# Front_End.net
KiCad netlist of a schematic drawn in Altium Designer
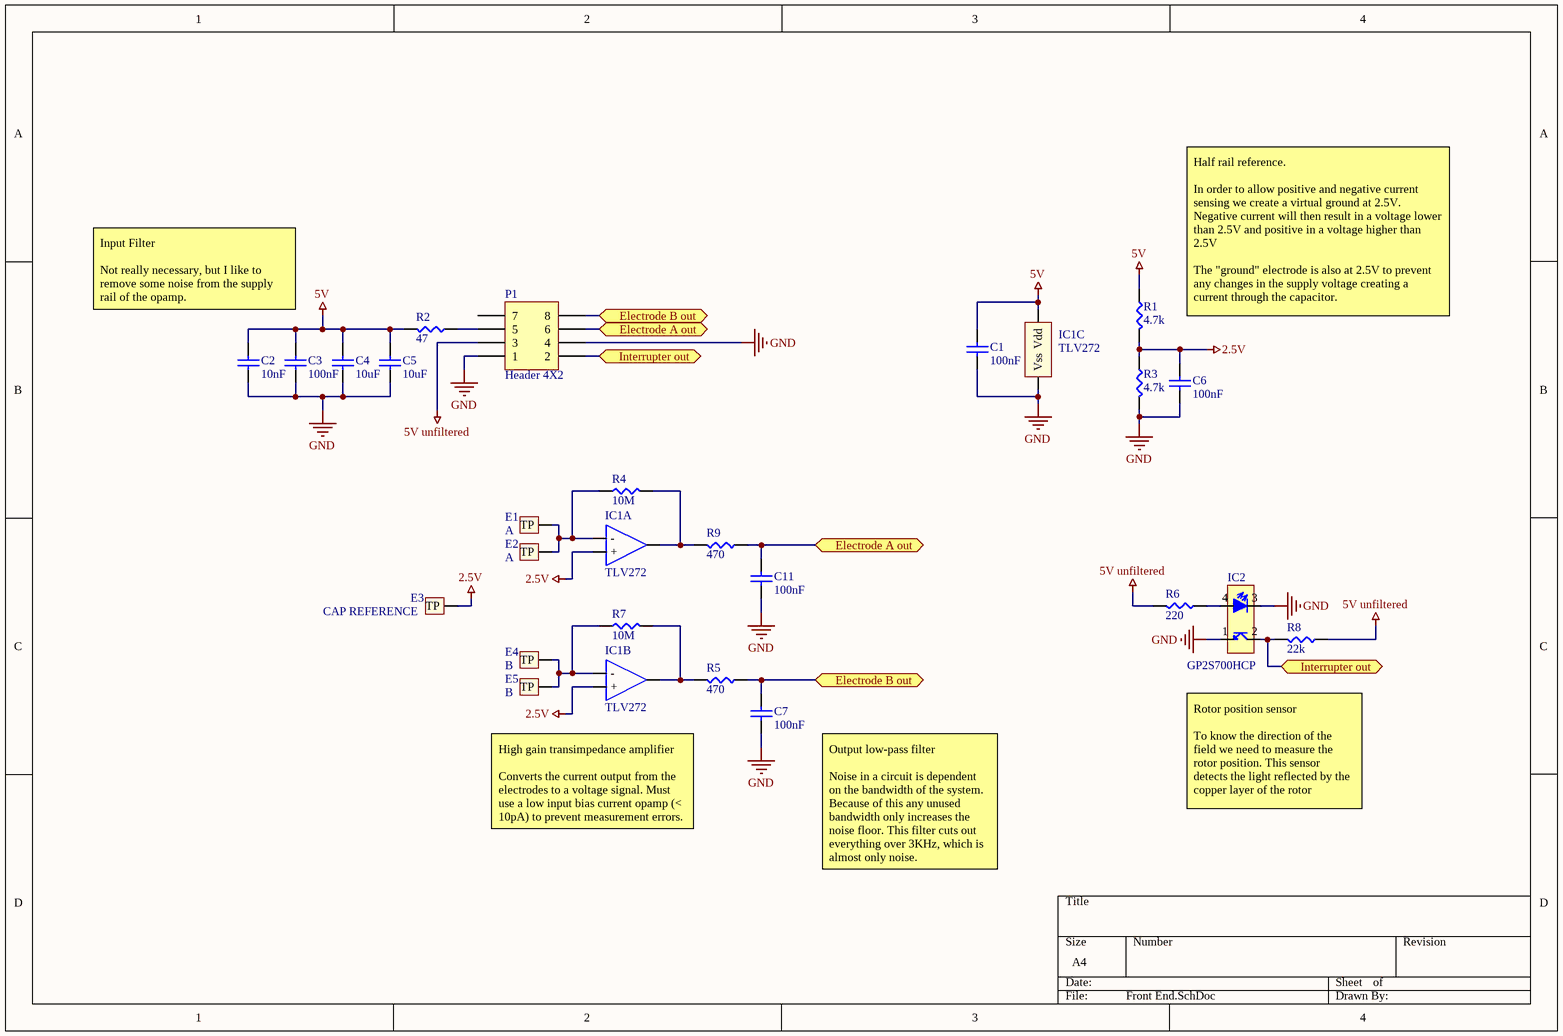
[diagram p0: Front End.SchDoc]

(export (version "E")
  (design (tool "Eeschema 10.0.6"))
  (components
    (comp (ref "C1") (value "100nF") (footprint "0805") (libsource (lib "stdLib") (part "Cap")))
    (comp (ref "C2") (value "10nF") (footprint "0805") (libsource (lib "stdLib") (part "Cap")))
    (comp (ref "C3") (value "100nF") (footprint "0805") (libsource (lib "stdLib") (part "Cap")))
    (comp (ref "C4") (value "10uF") (footprint "0805") (libsource (lib "stdLib") (part "Cap")))
    (comp (ref "C5") (value "10uF") (footprint "0805") (libsource (lib "stdLib") (part "Cap")))
    (comp (ref "C6") (value "100nF") (footprint "0805") (libsource (lib "stdLib") (part "Cap")))
    (comp (ref "C7") (value "100nF") (footprint "0805") (libsource (lib "stdLib") (part "Cap")))
    (comp (ref "C11") (value "100nF") (footprint "0805") (libsource (lib "stdLib") (part "Cap")))
    (comp (ref "E1") (value "A") (footprint "TESTPOINT_THT") (libsource (lib "stdLib") (part "Test Point")))
    (comp (ref "E2") (value "A") (footprint "TESTPOINT_THT") (libsource (lib "stdLib") (part "Test Point")))
    (comp (ref "E3")
      (value "CAP REFERENCE")
      (footprint "TESTPOINT_THT")
      (libsource (lib "stdLib") (part "Test Point"))
    )
    (comp (ref "E4") (value "B") (footprint "TESTPOINT_THT") (libsource (lib "stdLib") (part "Test Point")))
    (comp (ref "E5") (value "B") (footprint "TESTPOINT_THT") (libsource (lib "stdLib") (part "Test Point")))
    (comp (ref "IC1") (value "TLV272") (footprint "SO 8") (libsource (lib "stdLib") (part "OpAmp Dual")))
    (comp (ref "IC2")
      (value "GP2S700HCP")
      (footprint "GP2S700HCP")
      (description "Optical reflection interrupter")
      (libsource (lib "stdLib") (part "GP2S700HCP"))
    )
    (comp (ref "P1")
      (value "Header 4X2")
      (footprint "HDR2X4")
      (description "Header, 4-Pin, Dual row")
      (fields (field (name "PUBLISHER") "Altium Limited"))
      (libsource (lib "Miscellaneous Connectors") (part "Header 4X2"))
    )
    (comp (ref "R1") (value "4.7k") (footprint "0805") (libsource (lib "stdLib") (part "Resistor")))
    (comp (ref "R2") (value "47") (footprint "0805") (libsource (lib "stdLib") (part "Resistor")))
    (comp (ref "R3") (value "4.7k") (footprint "0805") (libsource (lib "stdLib") (part "Resistor")))
    (comp (ref "R4") (value "10M") (footprint "0805") (libsource (lib "stdLib") (part "Resistor")))
    (comp (ref "R5") (value "470") (footprint "0805") (libsource (lib "stdLib") (part "Resistor")))
    (comp (ref "R6") (value "220") (footprint "0805") (libsource (lib "stdLib") (part "Resistor")))
    (comp (ref "R7") (value "10M") (footprint "0805") (libsource (lib "stdLib") (part "Resistor")))
    (comp (ref "R8") (value "22k") (footprint "0805") (libsource (lib "stdLib") (part "Resistor")))
    (comp (ref "R9") (value "470") (footprint "0805") (libsource (lib "stdLib") (part "Resistor")))
  )
  (nets
    (net (code "1") (name "/Electrode A out") (class "Default")
      (node (ref "C11") (pin "2") (pinfunction "2_2") (pintype "passive"))
      (node (ref "P1") (pin "6") (pinfunction "6_6") (pintype "passive"))
      (node (ref "R9") (pin "1") (pinfunction "1_1") (pintype "passive"))
    )
    (net (code "2") (name "/Electrode B out") (class "Default")
      (node (ref "C7") (pin "2") (pinfunction "2_2") (pintype "passive"))
      (node (ref "P1") (pin "8") (pinfunction "8_8") (pintype "passive"))
      (node (ref "R5") (pin "1") (pinfunction "1_1") (pintype "passive"))
    )
    (net (code "3") (name "/Interrupter out") (class "Default")
      (node (ref "IC2") (pin "2") (pinfunction "2_2") (pintype "passive"))
      (node (ref "P1") (pin "2") (pinfunction "2_2") (pintype "passive"))
      (node (ref "R8") (pin "2") (pinfunction "2_2") (pintype "passive"))
    )
    (net (code "4") (name "2.5V") (class "Default")
      (node (ref "C6") (pin "2") (pinfunction "2_2") (pintype "passive"))
      (node (ref "E3") (pin "1") (pinfunction "TP_1") (pintype "passive"))
      (node (ref "IC1") (pin "IN1_+") (pinfunction "+_IN1_+") (pintype "passive"))
      (node (ref "IC1") (pin "IN2_+") (pinfunction "+_IN2_+") (pintype "passive"))
      (node (ref "R1") (pin "2") (pinfunction "2_2") (pintype "passive"))
      (node (ref "R3") (pin "1") (pinfunction "1_1") (pintype "passive"))
    )
    (net (code "5") (name "5V") (class "Default")
      (node (ref "C1") (pin "2") (pinfunction "2_2") (pintype "passive"))
      (node (ref "C2") (pin "2") (pinfunction "2_2") (pintype "passive"))
      (node (ref "C3") (pin "2") (pinfunction "2_2") (pintype "passive"))
      (node (ref "C4") (pin "2") (pinfunction "2_2") (pintype "passive"))
      (node (ref "C5") (pin "2") (pinfunction "2_2") (pintype "passive"))
      (node (ref "IC1") (pin "Vdd") (pinfunction "Vdd_Vdd") (pintype "passive"))
      (node (ref "R1") (pin "1") (pinfunction "1_1") (pintype "passive"))
      (node (ref "R2") (pin "2") (pinfunction "2_2") (pintype "passive"))
    )
    (net (code "6") (name "5V unfiltered") (class "Default")
      (node (ref "P1") (pin "3") (pinfunction "3_3") (pintype "passive"))
      (node (ref "R6") (pin "2") (pinfunction "2_2") (pintype "passive"))
      (node (ref "R8") (pin "1") (pinfunction "1_1") (pintype "passive"))
    )
    (net (code "7") (name "GND") (class "Default")
      (node (ref "C1") (pin "1") (pinfunction "1_1") (pintype "passive"))
      (node (ref "C11") (pin "1") (pinfunction "1_1") (pintype "passive"))
      (node (ref "C2") (pin "1") (pinfunction "1_1") (pintype "passive"))
      (node (ref "C3") (pin "1") (pinfunction "1_1") (pintype "passive"))
      (node (ref "C4") (pin "1") (pinfunction "1_1") (pintype "passive"))
      (node (ref "C5") (pin "1") (pinfunction "1_1") (pintype "passive"))
      (node (ref "C6") (pin "1") (pinfunction "1_1") (pintype "passive"))
      (node (ref "C7") (pin "1") (pinfunction "1_1") (pintype "passive"))
      (node (ref "IC1") (pin "Vss") (pinfunction "Vss_Vss") (pintype "passive"))
      (node (ref "IC2") (pin "1") (pinfunction "1_1") (pintype "passive"))
      (node (ref "IC2") (pin "3") (pinfunction "3_3") (pintype "passive"))
      (node (ref "P1") (pin "1") (pinfunction "1_1") (pintype "passive"))
      (node (ref "P1") (pin "4") (pinfunction "4_4") (pintype "passive"))
      (node (ref "R3") (pin "2") (pinfunction "2_2") (pintype "passive"))
    )
    (net (code "8") (name "Net-(E1-TP)") (class "Default")
      (node (ref "E1") (pin "1") (pinfunction "TP_1") (pintype "passive"))
      (node (ref "E2") (pin "1") (pinfunction "TP_1") (pintype "passive"))
      (node (ref "IC1") (pin "IN1-") (pinfunction "-_IN1-") (pintype "passive"))
      (node (ref "R4") (pin "1") (pinfunction "1_1") (pintype "passive"))
    )
    (net (code "9") (name "Net-(E4-TP)") (class "Default")
      (node (ref "E4") (pin "1") (pinfunction "TP_1") (pintype "passive"))
      (node (ref "E5") (pin "1") (pinfunction "TP_1") (pintype "passive"))
      (node (ref "IC1") (pin "IN2_-") (pinfunction "-_IN2_-") (pintype "passive"))
      (node (ref "R7") (pin "1") (pinfunction "1_1") (pintype "passive"))
    )
    (net (code "10") (name "Net-(IC1A-Out)") (class "Default")
      (node (ref "IC1") (pin "OUT1") (pinfunction "Out_OUT1") (pintype "passive"))
      (node (ref "R4") (pin "2") (pinfunction "2_2") (pintype "passive"))
      (node (ref "R9") (pin "2") (pinfunction "2_2") (pintype "passive"))
    )
    (net (code "11") (name "Net-(IC1B-Out)") (class "Default")
      (node (ref "IC1") (pin "OUT2") (pinfunction "Out_OUT2") (pintype "passive"))
      (node (ref "R5") (pin "2") (pinfunction "2_2") (pintype "passive"))
      (node (ref "R7") (pin "2") (pinfunction "2_2") (pintype "passive"))
    )
    (net (code "12") (name "Net-(IC2-Pad4)") (class "Default")
      (node (ref "IC2") (pin "4") (pinfunction "4_4") (pintype "passive"))
      (node (ref "R6") (pin "1") (pinfunction "1_1") (pintype "passive"))
    )
    (net (code "13") (name "Net-(P1-Pad5)") (class "Default")
      (node (ref "P1") (pin "5") (pinfunction "5_5") (pintype "passive"))
      (node (ref "R2") (pin "1") (pinfunction "1_1") (pintype "passive"))
    )
    (net (code "14") (name "unconnected-(P1-Pad7)") (class "Default")
      (node (ref "P1") (pin "7") (pinfunction "7_7") (pintype "passive"))
    )
  )
)
